# das_updated_v7.net
KiCad netlist of a schematic drawn in EAGLE
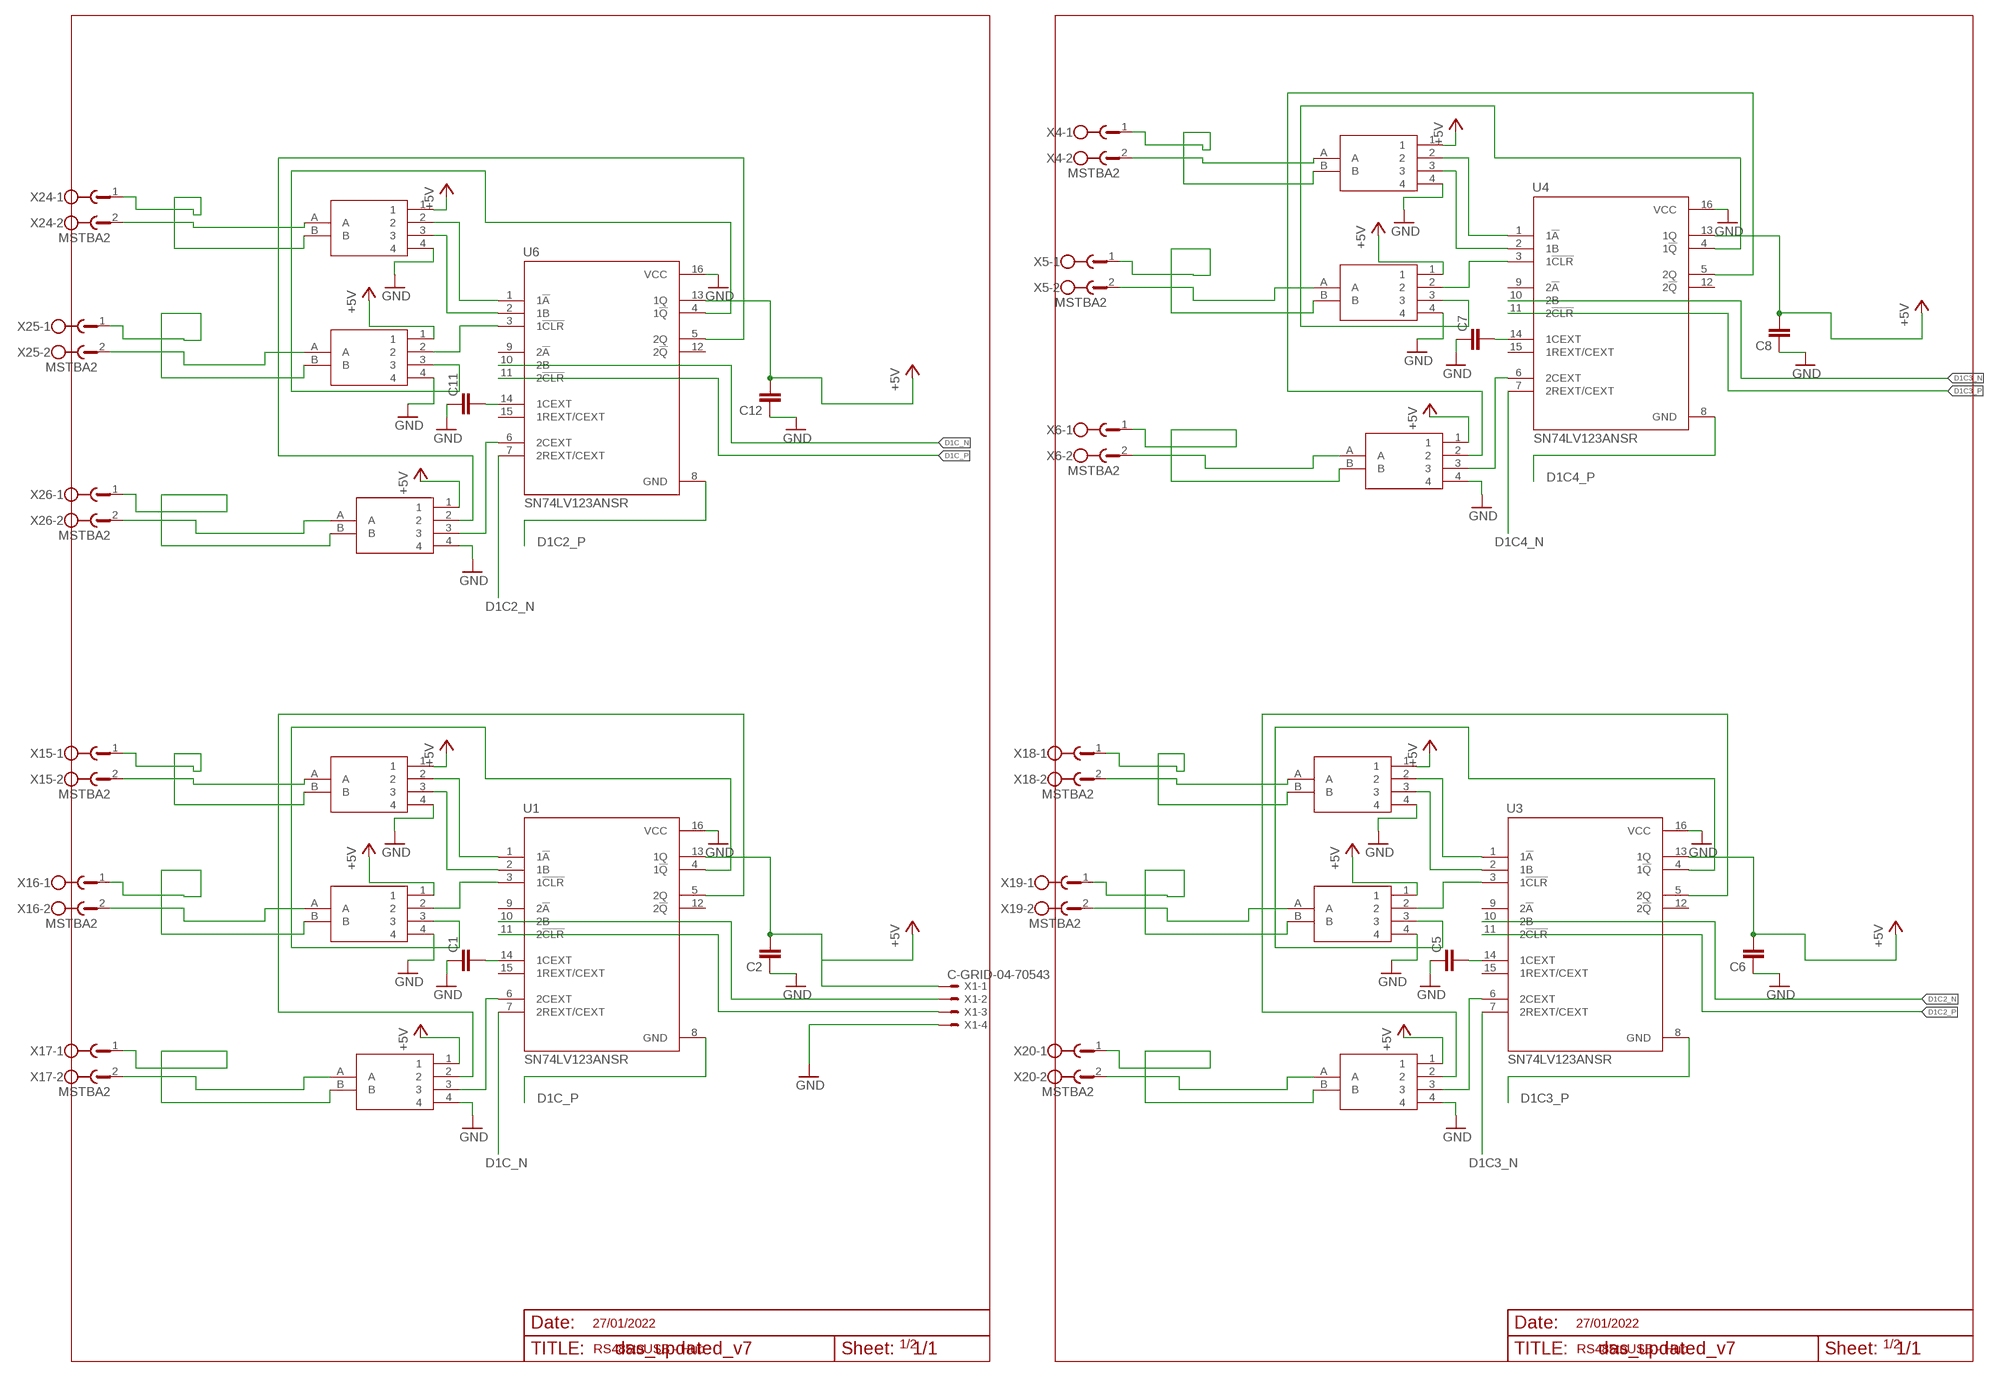
[diagram p0: schematic, sheet 1, part 1 of 2]
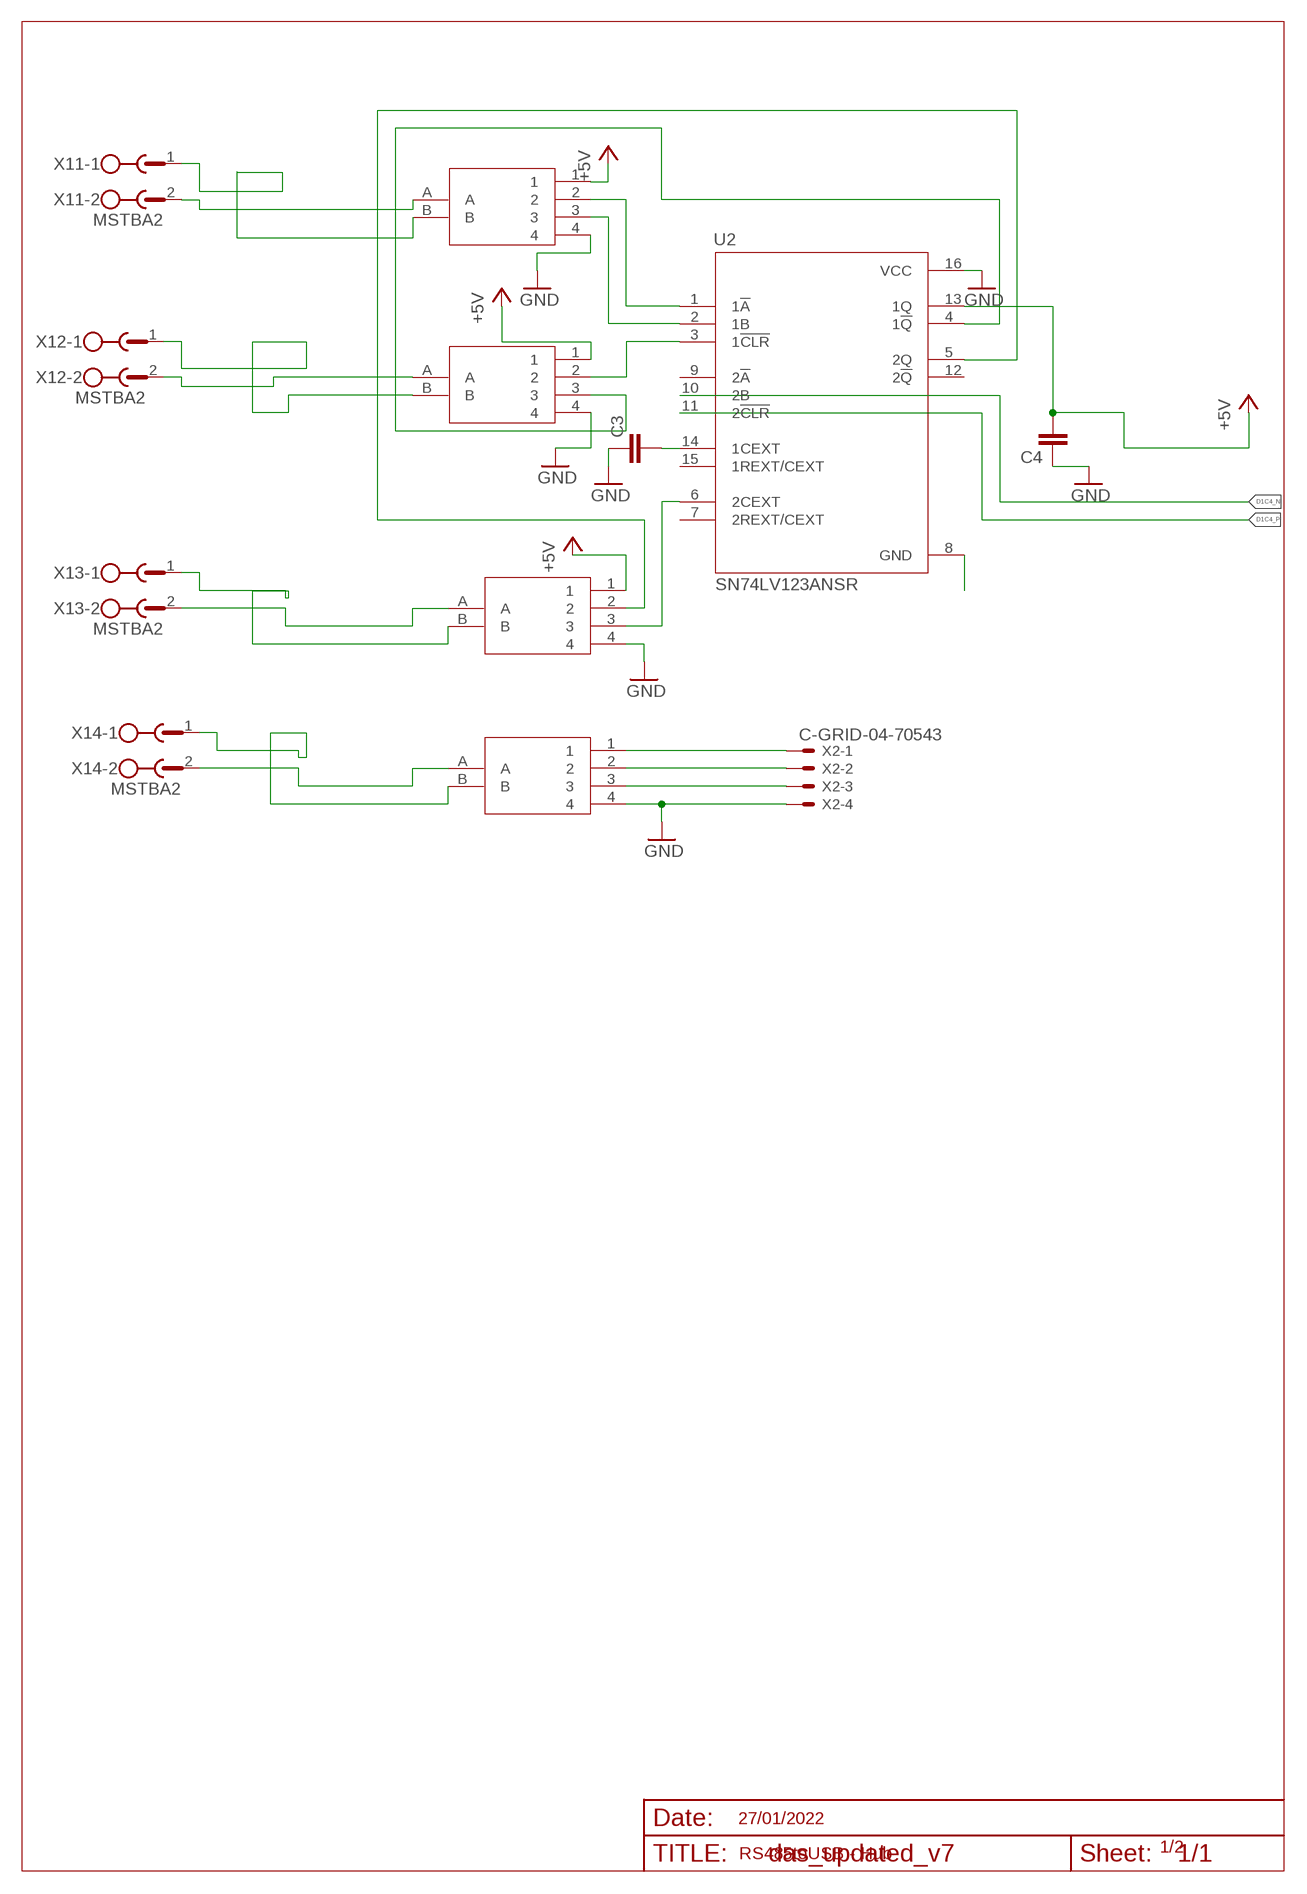
[diagram p1: schematic, sheet 1, part 2 of 2]

(export (version "E")
  (design (tool "Eeschema 10.0.6"))
  (components
    (comp (ref "C1")
      (value "C-EUC0603K")
      (footprint "eagle-import:C0603K")
      (libsource (lib "eagle-import") (part "C-EUC0603K"))
    )
    (comp (ref "C2")
      (value "C-EUC0603K")
      (footprint "eagle-import:C0603K")
      (libsource (lib "eagle-import") (part "C-EUC0603K"))
    )
    (comp (ref "C3")
      (value "C-EUC0603K")
      (footprint "eagle-import:C0603K")
      (libsource (lib "eagle-import") (part "C-EUC0603K"))
    )
    (comp (ref "C4")
      (value "C-EUC0603K")
      (footprint "eagle-import:C0603K")
      (libsource (lib "eagle-import") (part "C-EUC0603K"))
    )
    (comp (ref "C5")
      (value "C-EUC0603K")
      (footprint "eagle-import:C0603K")
      (libsource (lib "eagle-import") (part "C-EUC0603K"))
    )
    (comp (ref "C6")
      (value "C-EUC0603K")
      (footprint "eagle-import:C0603K")
      (libsource (lib "eagle-import") (part "C-EUC0603K"))
    )
    (comp (ref "C7")
      (value "C-EUC0603K")
      (footprint "eagle-import:C0603K")
      (libsource (lib "eagle-import") (part "C-EUC0603K"))
    )
    (comp (ref "C8")
      (value "C-EUC0603K")
      (footprint "eagle-import:C0603K")
      (libsource (lib "eagle-import") (part "C-EUC0603K"))
    )
    (comp (ref "C11")
      (value "C-EUC0603K")
      (footprint "eagle-import:C0603K")
      (libsource (lib "eagle-import") (part "C-EUC0603K"))
    )
    (comp (ref "C12")
      (value "C-EUC0603K")
      (footprint "eagle-import:C0603K")
      (libsource (lib "eagle-import") (part "C-EUC0603K"))
    )
    (comp (ref "U1")
      (value "SN74LV123ANSR")
      (footprint "eagle-import:SOIC127P780X200-16N")
      (fields (field (name "MF") "Texas Instruments"))
      (libsource (lib "eagle-import") (part "SN74LV123ANSR"))
    )
    (comp (ref "U2")
      (value "SN74LV123ANSR")
      (footprint "eagle-import:SOIC127P780X200-16N")
      (fields (field (name "MF") "Texas Instruments"))
      (libsource (lib "eagle-import") (part "SN74LV123ANSR"))
    )
    (comp (ref "U3")
      (value "SN74LV123ANSR")
      (footprint "eagle-import:SOIC127P780X200-16N")
      (fields (field (name "MF") "Texas Instruments"))
      (libsource (lib "eagle-import") (part "SN74LV123ANSR"))
    )
    (comp (ref "U4")
      (value "SN74LV123ANSR")
      (footprint "eagle-import:SOIC127P780X200-16N")
      (fields (field (name "MF") "Texas Instruments"))
      (libsource (lib "eagle-import") (part "SN74LV123ANSR"))
    )
    (comp (ref "U6")
      (value "SN74LV123ANSR")
      (footprint "eagle-import:SOIC127P780X200-16N")
      (fields (field (name "MF") "Texas Instruments"))
      (libsource (lib "eagle-import") (part "SN74LV123ANSR"))
    )
    (comp (ref "USB2RS1")
      (value "USB2RS485")
      (footprint "eagle-import:USB2RS485")
      (libsource (lib "eagle-import") (part "USB2RS485"))
    )
    (comp (ref "USB2RS2")
      (value "USB2RS485")
      (footprint "eagle-import:USB2RS485")
      (libsource (lib "eagle-import") (part "USB2RS485"))
    )
    (comp (ref "USB2RS3")
      (value "USB2RS485")
      (footprint "eagle-import:USB2RS485")
      (libsource (lib "eagle-import") (part "USB2RS485"))
    )
    (comp (ref "USB2RS4")
      (value "USB2RS485")
      (footprint "eagle-import:USB2RS485")
      (libsource (lib "eagle-import") (part "USB2RS485"))
    )
    (comp (ref "USB2RS5")
      (value "USB2RS485")
      (footprint "eagle-import:USB2RS485")
      (libsource (lib "eagle-import") (part "USB2RS485"))
    )
    (comp (ref "USB2RS6")
      (value "USB2RS485")
      (footprint "eagle-import:USB2RS485")
      (libsource (lib "eagle-import") (part "USB2RS485"))
    )
    (comp (ref "USB2RS7")
      (value "USB2RS485")
      (footprint "eagle-import:USB2RS485")
      (libsource (lib "eagle-import") (part "USB2RS485"))
    )
    (comp (ref "USB2RS8")
      (value "USB2RS485")
      (footprint "eagle-import:USB2RS485")
      (libsource (lib "eagle-import") (part "USB2RS485"))
    )
    (comp (ref "USB2RS9")
      (value "USB2RS485")
      (footprint "eagle-import:USB2RS485")
      (libsource (lib "eagle-import") (part "USB2RS485"))
    )
    (comp (ref "USB2RS10")
      (value "USB2RS485")
      (footprint "eagle-import:USB2RS485")
      (libsource (lib "eagle-import") (part "USB2RS485"))
    )
    (comp (ref "USB2RS11")
      (value "USB2RS485")
      (footprint "eagle-import:USB2RS485")
      (libsource (lib "eagle-import") (part "USB2RS485"))
    )
    (comp (ref "USB2RS12")
      (value "USB2RS485")
      (footprint "eagle-import:USB2RS485")
      (libsource (lib "eagle-import") (part "USB2RS485"))
    )
    (comp (ref "USB2RS13")
      (value "USB2RS485")
      (footprint "eagle-import:USB2RS485")
      (libsource (lib "eagle-import") (part "USB2RS485"))
    )
    (comp (ref "USB2RS17")
      (value "USB2RS485")
      (footprint "eagle-import:USB2RS485")
      (libsource (lib "eagle-import") (part "USB2RS485"))
    )
    (comp (ref "USB2RS18")
      (value "USB2RS485")
      (footprint "eagle-import:USB2RS485")
      (libsource (lib "eagle-import") (part "USB2RS485"))
    )
    (comp (ref "USB2RS19")
      (value "USB2RS485")
      (footprint "eagle-import:USB2RS485")
      (libsource (lib "eagle-import") (part "USB2RS485"))
    )
    (comp (ref "X1")
      (value "C-GRID-04-70543")
      (footprint "eagle-import:70543-04")
      (fields (field (name "MF") "MOLEX"))
      (libsource (lib "eagle-import") (part "C-GRID-04-70543"))
    )
    (comp (ref "X2")
      (value "C-GRID-04-70543")
      (footprint "eagle-import:70543-04")
      (fields (field (name "MF") "MOLEX"))
      (libsource (lib "eagle-import") (part "C-GRID-04-70543"))
    )
    (comp (ref "X4")
      (value "MSTBA2")
      (footprint "eagle-import:MSTBA2")
      (fields (field (name "MF") "FARNELL") (field (name "MPN") "1757242"))
      (libsource (lib "eagle-import") (part "MSTBA2"))
    )
    (comp (ref "X5")
      (value "MSTBA2")
      (footprint "eagle-import:MSTBA2")
      (fields (field (name "MF") "FARNELL") (field (name "MPN") "1757242"))
      (libsource (lib "eagle-import") (part "MSTBA2"))
    )
    (comp (ref "X6")
      (value "MSTBA2")
      (footprint "eagle-import:MSTBA2")
      (fields (field (name "MF") "FARNELL") (field (name "MPN") "1757242"))
      (libsource (lib "eagle-import") (part "MSTBA2"))
    )
    (comp (ref "X11")
      (value "MSTBA2")
      (footprint "eagle-import:MSTBA2")
      (fields (field (name "MF") "FARNELL") (field (name "MPN") "1757242"))
      (libsource (lib "eagle-import") (part "MSTBA2"))
    )
    (comp (ref "X12")
      (value "MSTBA2")
      (footprint "eagle-import:MSTBA2")
      (fields (field (name "MF") "FARNELL") (field (name "MPN") "1757242"))
      (libsource (lib "eagle-import") (part "MSTBA2"))
    )
    (comp (ref "X13")
      (value "MSTBA2")
      (footprint "eagle-import:MSTBA2")
      (fields (field (name "MF") "FARNELL") (field (name "MPN") "1757242"))
      (libsource (lib "eagle-import") (part "MSTBA2"))
    )
    (comp (ref "X14")
      (value "MSTBA2")
      (footprint "eagle-import:MSTBA2")
      (fields (field (name "MF") "FARNELL") (field (name "MPN") "1757242"))
      (libsource (lib "eagle-import") (part "MSTBA2"))
    )
    (comp (ref "X15")
      (value "MSTBA2")
      (footprint "eagle-import:MSTBA2")
      (fields (field (name "MF") "FARNELL") (field (name "MPN") "1757242"))
      (libsource (lib "eagle-import") (part "MSTBA2"))
    )
    (comp (ref "X16")
      (value "MSTBA2")
      (footprint "eagle-import:MSTBA2")
      (fields (field (name "MF") "FARNELL") (field (name "MPN") "1757242"))
      (libsource (lib "eagle-import") (part "MSTBA2"))
    )
    (comp (ref "X17")
      (value "MSTBA2")
      (footprint "eagle-import:MSTBA2")
      (fields (field (name "MF") "FARNELL") (field (name "MPN") "1757242"))
      (libsource (lib "eagle-import") (part "MSTBA2"))
    )
    (comp (ref "X18")
      (value "MSTBA2")
      (footprint "eagle-import:MSTBA2")
      (fields (field (name "MF") "FARNELL") (field (name "MPN") "1757242"))
      (libsource (lib "eagle-import") (part "MSTBA2"))
    )
    (comp (ref "X19")
      (value "MSTBA2")
      (footprint "eagle-import:MSTBA2")
      (fields (field (name "MF") "FARNELL") (field (name "MPN") "1757242"))
      (libsource (lib "eagle-import") (part "MSTBA2"))
    )
    (comp (ref "X20")
      (value "MSTBA2")
      (footprint "eagle-import:MSTBA2")
      (fields (field (name "MF") "FARNELL") (field (name "MPN") "1757242"))
      (libsource (lib "eagle-import") (part "MSTBA2"))
    )
    (comp (ref "X24")
      (value "MSTBA2")
      (footprint "eagle-import:MSTBA2")
      (fields (field (name "MF") "FARNELL") (field (name "MPN") "1757242"))
      (libsource (lib "eagle-import") (part "MSTBA2"))
    )
    (comp (ref "X25")
      (value "MSTBA2")
      (footprint "eagle-import:MSTBA2")
      (fields (field (name "MF") "FARNELL") (field (name "MPN") "1757242"))
      (libsource (lib "eagle-import") (part "MSTBA2"))
    )
    (comp (ref "X26")
      (value "MSTBA2")
      (footprint "eagle-import:MSTBA2")
      (fields (field (name "MF") "FARNELL") (field (name "MPN") "1757242"))
      (libsource (lib "eagle-import") (part "MSTBA2"))
    )
  )
  (nets
    (net (code "1") (name "+5V") (class "Default")
      (node (ref "C12") (pin "2") (pinfunction "2_2") (pintype "passive"))
      (node (ref "C2") (pin "2") (pinfunction "2_2") (pintype "passive"))
      (node (ref "C4") (pin "2") (pinfunction "2_2") (pintype "passive"))
      (node (ref "C6") (pin "2") (pinfunction "2_2") (pintype "passive"))
      (node (ref "C8") (pin "2") (pinfunction "2_2") (pintype "passive"))
      (node (ref "U1") (pin "13") (pinfunction "1Q_13") (pintype "output"))
      (node (ref "U2") (pin "13") (pinfunction "1Q_13") (pintype "output"))
      (node (ref "U3") (pin "13") (pinfunction "1Q_13") (pintype "output"))
      (node (ref "U4") (pin "13") (pinfunction "1Q_13") (pintype "output"))
      (node (ref "U6") (pin "13") (pinfunction "1Q_13") (pintype "output"))
      (node (ref "USB2RS1") (pin "1") (pinfunction "1_1") (pintype "bidirectional"))
      (node (ref "USB2RS10") (pin "1") (pinfunction "1_1") (pintype "bidirectional"))
      (node (ref "USB2RS11") (pin "1") (pinfunction "1_1") (pintype "bidirectional"))
      (node (ref "USB2RS12") (pin "1") (pinfunction "1_1") (pintype "bidirectional"))
      (node (ref "USB2RS13") (pin "1") (pinfunction "1_1") (pintype "bidirectional"))
      (node (ref "USB2RS17") (pin "1") (pinfunction "1_1") (pintype "bidirectional"))
      (node (ref "USB2RS18") (pin "1") (pinfunction "1_1") (pintype "bidirectional"))
      (node (ref "USB2RS19") (pin "1") (pinfunction "1_1") (pintype "bidirectional"))
      (node (ref "USB2RS2") (pin "1") (pinfunction "1_1") (pintype "bidirectional"))
      (node (ref "USB2RS3") (pin "1") (pinfunction "1_1") (pintype "bidirectional"))
      (node (ref "USB2RS4") (pin "1") (pinfunction "1_1") (pintype "bidirectional"))
      (node (ref "USB2RS5") (pin "1") (pinfunction "1_1") (pintype "bidirectional"))
      (node (ref "USB2RS6") (pin "1") (pinfunction "1_1") (pintype "bidirectional"))
      (node (ref "USB2RS7") (pin "1") (pinfunction "1_1") (pintype "bidirectional"))
      (node (ref "USB2RS9") (pin "1") (pinfunction "1_1") (pintype "bidirectional"))
      (node (ref "X1") (pin "1") (pinfunction "S_1") (pintype "passive"))
    )
    (net (code "2") (name "D1C2_N") (class "Default")
      (node (ref "U3") (pin "10") (pinfunction "2B_10") (pintype "input"))
      (node (ref "U6") (pin "7") (pinfunction "2REXT/CEXT_7") (pintype "bidirectional"))
    )
    (net (code "3") (name "D1C2_P") (class "Default")
      (node (ref "U3") (pin "11") (pinfunction "2~{CLR}_11") (pintype "input"))
      (node (ref "U6") (pin "8") (pinfunction "GND_8") (pintype "power_in"))
    )
    (net (code "4") (name "D1C3_N") (class "Default")
      (node (ref "U3") (pin "7") (pinfunction "2REXT/CEXT_7") (pintype "bidirectional"))
      (node (ref "U4") (pin "10") (pinfunction "2B_10") (pintype "input"))
    )
    (net (code "5") (name "D1C3_P") (class "Default")
      (node (ref "U3") (pin "8") (pinfunction "GND_8") (pintype "power_in"))
      (node (ref "U4") (pin "11") (pinfunction "2~{CLR}_11") (pintype "input"))
    )
    (net (code "6") (name "D1C4_N") (class "Default")
      (node (ref "U2") (pin "10") (pinfunction "2B_10") (pintype "input"))
      (node (ref "U4") (pin "7") (pinfunction "2REXT/CEXT_7") (pintype "bidirectional"))
    )
    (net (code "7") (name "D1C4_P") (class "Default")
      (node (ref "U2") (pin "11") (pinfunction "2~{CLR}_11") (pintype "input"))
      (node (ref "U4") (pin "8") (pinfunction "GND_8") (pintype "power_in"))
    )
    (net (code "8") (name "D1C_N") (class "Default")
      (node (ref "U1") (pin "7") (pinfunction "2REXT/CEXT_7") (pintype "bidirectional"))
      (node (ref "U6") (pin "10") (pinfunction "2B_10") (pintype "input"))
    )
    (net (code "9") (name "D1C_P") (class "Default")
      (node (ref "U1") (pin "8") (pinfunction "GND_8") (pintype "power_in"))
      (node (ref "U6") (pin "11") (pinfunction "2~{CLR}_11") (pintype "input"))
    )
    (net (code "10") (name "GND") (class "Default")
      (node (ref "C1") (pin "1") (pinfunction "1_1") (pintype "passive"))
      (node (ref "C11") (pin "1") (pinfunction "1_1") (pintype "passive"))
      (node (ref "C12") (pin "1") (pinfunction "1_1") (pintype "passive"))
      (node (ref "C2") (pin "1") (pinfunction "1_1") (pintype "passive"))
      (node (ref "C3") (pin "1") (pinfunction "1_1") (pintype "passive"))
      (node (ref "C4") (pin "1") (pinfunction "1_1") (pintype "passive"))
      (node (ref "C5") (pin "1") (pinfunction "1_1") (pintype "passive"))
      (node (ref "C6") (pin "1") (pinfunction "1_1") (pintype "passive"))
      (node (ref "C7") (pin "1") (pinfunction "1_1") (pintype "passive"))
      (node (ref "C8") (pin "1") (pinfunction "1_1") (pintype "passive"))
      (node (ref "U1") (pin "16") (pinfunction "VCC_16") (pintype "power_in"))
      (node (ref "U2") (pin "16") (pinfunction "VCC_16") (pintype "power_in"))
      (node (ref "U3") (pin "16") (pinfunction "VCC_16") (pintype "power_in"))
      (node (ref "U4") (pin "16") (pinfunction "VCC_16") (pintype "power_in"))
      (node (ref "U6") (pin "16") (pinfunction "VCC_16") (pintype "power_in"))
      (node (ref "USB2RS1") (pin "4") (pinfunction "4_4") (pintype "bidirectional"))
      (node (ref "USB2RS10") (pin "4") (pinfunction "4_4") (pintype "bidirectional"))
      (node (ref "USB2RS11") (pin "4") (pinfunction "4_4") (pintype "bidirectional"))
      (node (ref "USB2RS12") (pin "4") (pinfunction "4_4") (pintype "bidirectional"))
      (node (ref "USB2RS13") (pin "4") (pinfunction "4_4") (pintype "bidirectional"))
      (node (ref "USB2RS17") (pin "4") (pinfunction "4_4") (pintype "bidirectional"))
      (node (ref "USB2RS18") (pin "4") (pinfunction "4_4") (pintype "bidirectional"))
      (node (ref "USB2RS19") (pin "4") (pinfunction "4_4") (pintype "bidirectional"))
      (node (ref "USB2RS2") (pin "4") (pinfunction "4_4") (pintype "bidirectional"))
      (node (ref "USB2RS3") (pin "4") (pinfunction "4_4") (pintype "bidirectional"))
      (node (ref "USB2RS4") (pin "4") (pinfunction "4_4") (pintype "bidirectional"))
      (node (ref "USB2RS5") (pin "4") (pinfunction "4_4") (pintype "bidirectional"))
      (node (ref "USB2RS6") (pin "4") (pinfunction "4_4") (pintype "bidirectional"))
      (node (ref "USB2RS7") (pin "4") (pinfunction "4_4") (pintype "bidirectional"))
      (node (ref "USB2RS8") (pin "4") (pinfunction "4_4") (pintype "bidirectional"))
      (node (ref "USB2RS9") (pin "4") (pinfunction "4_4") (pintype "bidirectional"))
      (node (ref "X1") (pin "4") (pinfunction "S_4") (pintype "passive"))
      (node (ref "X2") (pin "4") (pinfunction "S_4") (pintype "passive"))
    )
    (net (code "11") (name "Net-(U1-1B)") (class "Default")
      (node (ref "U1") (pin "2") (pinfunction "1B_2") (pintype "input"))
      (node (ref "USB2RS1") (pin "3") (pinfunction "3_3") (pintype "bidirectional"))
    )
    (net (code "12") (name "Net-(U1-1CEXT)") (class "Default")
      (node (ref "C1") (pin "2") (pinfunction "2_2") (pintype "passive"))
      (node (ref "U1") (pin "14") (pinfunction "1CEXT_14") (pintype "bidirectional"))
    )
    (net (code "13") (name "Net-(U1-1~{A})") (class "Default")
      (node (ref "U1") (pin "1") (pinfunction "1~{A}_1") (pintype "input"))
      (node (ref "USB2RS1") (pin "2") (pinfunction "2_2") (pintype "bidirectional"))
    )
    (net (code "14") (name "Net-(U1-1~{CLR})") (class "Default")
      (node (ref "U1") (pin "3") (pinfunction "1~{CLR}_3") (pintype "input"))
      (node (ref "USB2RS2") (pin "2") (pinfunction "2_2") (pintype "bidirectional"))
    )
    (net (code "15") (name "Net-(U1-1~{Q})") (class "Default")
      (node (ref "U1") (pin "4") (pinfunction "1~{Q}_4") (pintype "output"))
      (node (ref "USB2RS2") (pin "3") (pinfunction "3_3") (pintype "bidirectional"))
    )
    (net (code "16") (name "Net-(U1-2B)") (class "Default")
      (node (ref "U1") (pin "10") (pinfunction "2B_10") (pintype "input"))
      (node (ref "X1") (pin "2") (pinfunction "S_2") (pintype "passive"))
    )
    (net (code "17") (name "Net-(U1-2CEXT)") (class "Default")
      (node (ref "U1") (pin "6") (pinfunction "2CEXT_6") (pintype "bidirectional"))
      (node (ref "USB2RS3") (pin "3") (pinfunction "3_3") (pintype "bidirectional"))
    )
    (net (code "18") (name "Net-(U1-2Q)") (class "Default")
      (node (ref "U1") (pin "5") (pinfunction "2Q_5") (pintype "output"))
      (node (ref "USB2RS3") (pin "2") (pinfunction "2_2") (pintype "bidirectional"))
    )
    (net (code "19") (name "Net-(U1-2~{CLR})") (class "Default")
      (node (ref "U1") (pin "11") (pinfunction "2~{CLR}_11") (pintype "input"))
      (node (ref "X1") (pin "3") (pinfunction "S_3") (pintype "passive"))
    )
    (net (code "20") (name "Net-(U2-1B)") (class "Default")
      (node (ref "U2") (pin "2") (pinfunction "1B_2") (pintype "input"))
      (node (ref "USB2RS5") (pin "3") (pinfunction "3_3") (pintype "bidirectional"))
    )
    (net (code "21") (name "Net-(U2-1CEXT)") (class "Default")
      (node (ref "C3") (pin "2") (pinfunction "2_2") (pintype "passive"))
      (node (ref "U2") (pin "14") (pinfunction "1CEXT_14") (pintype "bidirectional"))
    )
    (net (code "22") (name "Net-(U2-1~{A})") (class "Default")
      (node (ref "U2") (pin "1") (pinfunction "1~{A}_1") (pintype "input"))
      (node (ref "USB2RS5") (pin "2") (pinfunction "2_2") (pintype "bidirectional"))
    )
    (net (code "23") (name "Net-(U2-1~{CLR})") (class "Default")
      (node (ref "U2") (pin "3") (pinfunction "1~{CLR}_3") (pintype "input"))
      (node (ref "USB2RS6") (pin "2") (pinfunction "2_2") (pintype "bidirectional"))
    )
    (net (code "24") (name "Net-(U2-1~{Q})") (class "Default")
      (node (ref "U2") (pin "4") (pinfunction "1~{Q}_4") (pintype "output"))
      (node (ref "USB2RS6") (pin "3") (pinfunction "3_3") (pintype "bidirectional"))
    )
    (net (code "25") (name "Net-(U2-2CEXT)") (class "Default")
      (node (ref "U2") (pin "6") (pinfunction "2CEXT_6") (pintype "bidirectional"))
      (node (ref "USB2RS7") (pin "3") (pinfunction "3_3") (pintype "bidirectional"))
    )
    (net (code "26") (name "Net-(U2-2Q)") (class "Default")
      (node (ref "U2") (pin "5") (pinfunction "2Q_5") (pintype "output"))
      (node (ref "USB2RS7") (pin "2") (pinfunction "2_2") (pintype "bidirectional"))
    )
    (net (code "27") (name "Net-(U3-1B)") (class "Default")
      (node (ref "U3") (pin "2") (pinfunction "1B_2") (pintype "input"))
      (node (ref "USB2RS4") (pin "3") (pinfunction "3_3") (pintype "bidirectional"))
    )
    (net (code "28") (name "Net-(U3-1CEXT)") (class "Default")
      (node (ref "C5") (pin "2") (pinfunction "2_2") (pintype "passive"))
      (node (ref "U3") (pin "14") (pinfunction "1CEXT_14") (pintype "bidirectional"))
    )
    (net (code "29") (name "Net-(U3-1~{A})") (class "Default")
      (node (ref "U3") (pin "1") (pinfunction "1~{A}_1") (pintype "input"))
      (node (ref "USB2RS4") (pin "2") (pinfunction "2_2") (pintype "bidirectional"))
    )
    (net (code "30") (name "Net-(U3-1~{CLR})") (class "Default")
      (node (ref "U3") (pin "3") (pinfunction "1~{CLR}_3") (pintype "input"))
      (node (ref "USB2RS9") (pin "2") (pinfunction "2_2") (pintype "bidirectional"))
    )
    (net (code "31") (name "Net-(U3-1~{Q})") (class "Default")
      (node (ref "U3") (pin "4") (pinfunction "1~{Q}_4") (pintype "output"))
      (node (ref "USB2RS9") (pin "3") (pinfunction "3_3") (pintype "bidirectional"))
    )
    (net (code "32") (name "Net-(U3-2CEXT)") (class "Default")
      (node (ref "U3") (pin "6") (pinfunction "2CEXT_6") (pintype "bidirectional"))
      (node (ref "USB2RS10") (pin "3") (pinfunction "3_3") (pintype "bidirectional"))
    )
    (net (code "33") (name "Net-(U3-2Q)") (class "Default")
      (node (ref "U3") (pin "5") (pinfunction "2Q_5") (pintype "output"))
      (node (ref "USB2RS10") (pin "2") (pinfunction "2_2") (pintype "bidirectional"))
    )
    (net (code "34") (name "Net-(U4-1B)") (class "Default")
      (node (ref "U4") (pin "2") (pinfunction "1B_2") (pintype "input"))
      (node (ref "USB2RS11") (pin "3") (pinfunction "3_3") (pintype "bidirectional"))
    )
    (net (code "35") (name "Net-(U4-1CEXT)") (class "Default")
      (node (ref "C7") (pin "2") (pinfunction "2_2") (pintype "passive"))
      (node (ref "U4") (pin "14") (pinfunction "1CEXT_14") (pintype "bidirectional"))
    )
    (net (code "36") (name "Net-(U4-1~{A})") (class "Default")
      (node (ref "U4") (pin "1") (pinfunction "1~{A}_1") (pintype "input"))
      (node (ref "USB2RS11") (pin "2") (pinfunction "2_2") (pintype "bidirectional"))
    )
    (net (code "37") (name "Net-(U4-1~{CLR})") (class "Default")
      (node (ref "U4") (pin "3") (pinfunction "1~{CLR}_3") (pintype "input"))
      (node (ref "USB2RS12") (pin "2") (pinfunction "2_2") (pintype "bidirectional"))
    )
    (net (code "38") (name "Net-(U4-1~{Q})") (class "Default")
      (node (ref "U4") (pin "4") (pinfunction "1~{Q}_4") (pintype "output"))
      (node (ref "USB2RS12") (pin "3") (pinfunction "3_3") (pintype "bidirectional"))
    )
    (net (code "39") (name "Net-(U4-2CEXT)") (class "Default")
      (node (ref "U4") (pin "6") (pinfunction "2CEXT_6") (pintype "bidirectional"))
      (node (ref "USB2RS13") (pin "3") (pinfunction "3_3") (pintype "bidirectional"))
    )
    (net (code "40") (name "Net-(U4-2Q)") (class "Default")
      (node (ref "U4") (pin "5") (pinfunction "2Q_5") (pintype "output"))
      (node (ref "USB2RS13") (pin "2") (pinfunction "2_2") (pintype "bidirectional"))
    )
    (net (code "41") (name "Net-(U6-1B)") (class "Default")
      (node (ref "U6") (pin "2") (pinfunction "1B_2") (pintype "input"))
      (node (ref "USB2RS17") (pin "3") (pinfunction "3_3") (pintype "bidirectional"))
    )
    (net (code "42") (name "Net-(U6-1CEXT)") (class "Default")
      (node (ref "C11") (pin "2") (pinfunction "2_2") (pintype "passive"))
      (node (ref "U6") (pin "14") (pinfunction "1CEXT_14") (pintype "bidirectional"))
    )
    (net (code "43") (name "Net-(U6-1~{A})") (class "Default")
      (node (ref "U6") (pin "1") (pinfunction "1~{A}_1") (pintype "input"))
      (node (ref "USB2RS17") (pin "2") (pinfunction "2_2") (pintype "bidirectional"))
    )
    (net (code "44") (name "Net-(U6-1~{CLR})") (class "Default")
      (node (ref "U6") (pin "3") (pinfunction "1~{CLR}_3") (pintype "input"))
      (node (ref "USB2RS18") (pin "2") (pinfunction "2_2") (pintype "bidirectional"))
    )
    (net (code "45") (name "Net-(U6-1~{Q})") (class "Default")
      (node (ref "U6") (pin "4") (pinfunction "1~{Q}_4") (pintype "output"))
      (node (ref "USB2RS18") (pin "3") (pinfunction "3_3") (pintype "bidirectional"))
    )
    (net (code "46") (name "Net-(U6-2CEXT)") (class "Default")
      (node (ref "U6") (pin "6") (pinfunction "2CEXT_6") (pintype "bidirectional"))
      (node (ref "USB2RS19") (pin "3") (pinfunction "3_3") (pintype "bidirectional"))
    )
    (net (code "47") (name "Net-(U6-2Q)") (class "Default")
      (node (ref "U6") (pin "5") (pinfunction "2Q_5") (pintype "output"))
      (node (ref "USB2RS19") (pin "2") (pinfunction "2_2") (pintype "bidirectional"))
    )
    (net (code "48") (name "Net-(USB2RS1-PadB)") (class "Default")
      (node (ref "USB2RS1") (pin "B") (pinfunction "B_B") (pintype "bidirectional"))
      (node (ref "X15") (pin "1") (pinfunction "1_1") (pintype "passive"))
    )
    (net (code "49") (name "Net-(USB2RS2-PadB)") (class "Default")
      (node (ref "USB2RS2") (pin "B") (pinfunction "B_B") (pintype "bidirectional"))
      (node (ref "X16") (pin "1") (pinfunction "1_1") (pintype "passive"))
    )
    (net (code "50") (name "Net-(USB2RS3-PadB)") (class "Default")
      (node (ref "USB2RS3") (pin "B") (pinfunction "B_B") (pintype "bidirectional"))
      (node (ref "X17") (pin "1") (pinfunction "1_1") (pintype "passive"))
    )
    (net (code "51") (name "Net-(USB2RS4-PadB)") (class "Default")
      (node (ref "USB2RS4") (pin "B") (pinfunction "B_B") (pintype "bidirectional"))
      (node (ref "X18") (pin "1") (pinfunction "1_1") (pintype "passive"))
    )
    (net (code "52") (name "Net-(USB2RS5-PadB)") (class "Default")
      (node (ref "USB2RS5") (pin "B") (pinfunction "B_B") (pintype "bidirectional"))
      (node (ref "X11") (pin "1") (pinfunction "1_1") (pintype "passive"))
    )
    (net (code "53") (name "Net-(USB2RS6-PadB)") (class "Default")
      (node (ref "USB2RS6") (pin "B") (pinfunction "B_B") (pintype "bidirectional"))
      (node (ref "X12") (pin "1") (pinfunction "1_1") (pintype "passive"))
    )
    (net (code "54") (name "Net-(USB2RS7-PadB)") (class "Default")
      (node (ref "USB2RS7") (pin "B") (pinfunction "B_B") (pintype "bidirectional"))
      (node (ref "X13") (pin "1") (pinfunction "1_1") (pintype "passive"))
    )
    (net (code "55") (name "Net-(USB2RS8-PadB)") (class "Default")
      (node (ref "USB2RS8") (pin "B") (pinfunction "B_B") (pintype "bidirectional"))
      (node (ref "X14") (pin "1") (pinfunction "1_1") (pintype "passive"))
    )
    (net (code "56") (name "Net-(USB2RS9-PadB)") (class "Default")
      (node (ref "USB2RS9") (pin "B") (pinfunction "B_B") (pintype "bidirectional"))
      (node (ref "X19") (pin "1") (pinfunction "1_1") (pintype "passive"))
    )
    (net (code "57") (name "Net-(USB2RS10-PadB)") (class "Default")
      (node (ref "USB2RS10") (pin "B") (pinfunction "B_B") (pintype "bidirectional"))
      (node (ref "X20") (pin "1") (pinfunction "1_1") (pintype "passive"))
    )
    (net (code "58") (name "Net-(USB2RS11-PadB)") (class "Default")
      (node (ref "USB2RS11") (pin "B") (pinfunction "B_B") (pintype "bidirectional"))
      (node (ref "X4") (pin "1") (pinfunction "1_1") (pintype "passive"))
    )
    (net (code "59") (name "Net-(USB2RS12-PadB)") (class "Default")
      (node (ref "USB2RS12") (pin "B") (pinfunction "B_B") (pintype "bidirectional"))
      (node (ref "X5") (pin "1") (pinfunction "1_1") (pintype "passive"))
    )
    (net (code "60") (name "Net-(USB2RS13-PadB)") (class "Default")
      (node (ref "USB2RS13") (pin "B") (pinfunction "B_B") (pintype "bidirectional"))
      (node (ref "X6") (pin "1") (pinfunction "1_1") (pintype "passive"))
    )
    (net (code "61") (name "Net-(USB2RS17-PadB)") (class "Default")
      (node (ref "USB2RS17") (pin "B") (pinfunction "B_B") (pintype "bidirectional"))
      (node (ref "X24") (pin "1") (pinfunction "1_1") (pintype "passive"))
    )
    (net (code "62") (name "Net-(USB2RS18-PadB)") (class "Default")
      (node (ref "USB2RS18") (pin "B") (pinfunction "B_B") (pintype "bidirectional"))
      (node (ref "X25") (pin "1") (pinfunction "1_1") (pintype "passive"))
    )
    (net (code "63") (name "Net-(USB2RS19-PadB)") (class "Default")
      (node (ref "USB2RS19") (pin "B") (pinfunction "B_B") (pintype "bidirectional"))
      (node (ref "X26") (pin "1") (pinfunction "1_1") (pintype "passive"))
    )
    (net (code "64") (name "Net-(X2A-S)") (class "Default")
      (node (ref "USB2RS8") (pin "1") (pinfunction "1_1") (pintype "bidirectional"))
      (node (ref "X2") (pin "1") (pinfunction "S_1") (pintype "passive"))
    )
    (net (code "65") (name "Net-(X2B-S)") (class "Default")
      (node (ref "USB2RS8") (pin "2") (pinfunction "2_2") (pintype "bidirectional"))
      (node (ref "X2") (pin "2") (pinfunction "S_2") (pintype "passive"))
    )
    (net (code "66") (name "Net-(X2C-S)") (class "Default")
      (node (ref "USB2RS8") (pin "3") (pinfunction "3_3") (pintype "bidirectional"))
      (node (ref "X2") (pin "3") (pinfunction "S_3") (pintype "passive"))
    )
    (net (code "67") (name "Net-(X4B-1)") (class "Default")
      (node (ref "USB2RS11") (pin "A") (pinfunction "A_A") (pintype "bidirectional"))
      (node (ref "X4") (pin "2") (pinfunction "1_2") (pintype "passive"))
    )
    (net (code "68") (name "Net-(X5B-1)") (class "Default")
      (node (ref "USB2RS12") (pin "A") (pinfunction "A_A") (pintype "bidirectional"))
      (node (ref "X5") (pin "2") (pinfunction "1_2") (pintype "passive"))
    )
    (net (code "69") (name "Net-(X6B-1)") (class "Default")
      (node (ref "USB2RS13") (pin "A") (pinfunction "A_A") (pintype "bidirectional"))
      (node (ref "X6") (pin "2") (pinfunction "1_2") (pintype "passive"))
    )
    (net (code "70") (name "Net-(X11B-1)") (class "Default")
      (node (ref "USB2RS5") (pin "A") (pinfunction "A_A") (pintype "bidirectional"))
      (node (ref "X11") (pin "2") (pinfunction "1_2") (pintype "passive"))
    )
    (net (code "71") (name "Net-(X12B-1)") (class "Default")
      (node (ref "USB2RS6") (pin "A") (pinfunction "A_A") (pintype "bidirectional"))
      (node (ref "X12") (pin "2") (pinfunction "1_2") (pintype "passive"))
    )
    (net (code "72") (name "Net-(X13B-1)") (class "Default")
      (node (ref "USB2RS7") (pin "A") (pinfunction "A_A") (pintype "bidirectional"))
      (node (ref "X13") (pin "2") (pinfunction "1_2") (pintype "passive"))
    )
    (net (code "73") (name "Net-(X14B-1)") (class "Default")
      (node (ref "USB2RS8") (pin "A") (pinfunction "A_A") (pintype "bidirectional"))
      (node (ref "X14") (pin "2") (pinfunction "1_2") (pintype "passive"))
    )
    (net (code "74") (name "Net-(X15B-1)") (class "Default")
      (node (ref "USB2RS1") (pin "A") (pinfunction "A_A") (pintype "bidirectional"))
      (node (ref "X15") (pin "2") (pinfunction "1_2") (pintype "passive"))
    )
    (net (code "75") (name "Net-(X16B-1)") (class "Default")
      (node (ref "USB2RS2") (pin "A") (pinfunction "A_A") (pintype "bidirectional"))
      (node (ref "X16") (pin "2") (pinfunction "1_2") (pintype "passive"))
    )
    (net (code "76") (name "Net-(X17B-1)") (class "Default")
      (node (ref "USB2RS3") (pin "A") (pinfunction "A_A") (pintype "bidirectional"))
      (node (ref "X17") (pin "2") (pinfunction "1_2") (pintype "passive"))
    )
    (net (code "77") (name "Net-(X18B-1)") (class "Default")
      (node (ref "USB2RS4") (pin "A") (pinfunction "A_A") (pintype "bidirectional"))
      (node (ref "X18") (pin "2") (pinfunction "1_2") (pintype "passive"))
    )
    (net (code "78") (name "Net-(X19B-1)") (class "Default")
      (node (ref "USB2RS9") (pin "A") (pinfunction "A_A") (pintype "bidirectional"))
      (node (ref "X19") (pin "2") (pinfunction "1_2") (pintype "passive"))
    )
    (net (code "79") (name "Net-(X20B-1)") (class "Default")
      (node (ref "USB2RS10") (pin "A") (pinfunction "A_A") (pintype "bidirectional"))
      (node (ref "X20") (pin "2") (pinfunction "1_2") (pintype "passive"))
    )
    (net (code "80") (name "Net-(X24B-1)") (class "Default")
      (node (ref "USB2RS17") (pin "A") (pinfunction "A_A") (pintype "bidirectional"))
      (node (ref "X24") (pin "2") (pinfunction "1_2") (pintype "passive"))
    )
    (net (code "81") (name "Net-(X25B-1)") (class "Default")
      (node (ref "USB2RS18") (pin "A") (pinfunction "A_A") (pintype "bidirectional"))
      (node (ref "X25") (pin "2") (pinfunction "1_2") (pintype "passive"))
    )
    (net (code "82") (name "Net-(X26B-1)") (class "Default")
      (node (ref "USB2RS19") (pin "A") (pinfunction "A_A") (pintype "bidirectional"))
      (node (ref "X26") (pin "2") (pinfunction "1_2") (pintype "passive"))
    )
    (net (code "83") (name "unconnected-(U1-1REXT{slash}CEXT-Pad15)") (class "Default")
      (node (ref "U1") (pin "15") (pinfunction "1REXT/CEXT_15") (pintype "bidirectional"))
    )
    (net (code "84") (name "unconnected-(U1-2~{A}-Pad9)") (class "Default")
      (node (ref "U1") (pin "9") (pinfunction "2~{A}_9") (pintype "input"))
    )
    (net (code "85") (name "unconnected-(U1-2~{Q}-Pad12)") (class "Default")
      (node (ref "U1") (pin "12") (pinfunction "2~{Q}_12") (pintype "output"))
    )
    (net (code "86") (name "unconnected-(U2-1REXT{slash}CEXT-Pad15)") (class "Default")
      (node (ref "U2") (pin "15") (pinfunction "1REXT/CEXT_15") (pintype "bidirectional"))
    )
    (net (code "87") (name "unconnected-(U2-2REXT{slash}CEXT-Pad7)") (class "Default")
      (node (ref "U2") (pin "7") (pinfunction "2REXT/CEXT_7") (pintype "bidirectional"))
    )
    (net (code "88") (name "unconnected-(U2-2~{A}-Pad9)") (class "Default")
      (node (ref "U2") (pin "9") (pinfunction "2~{A}_9") (pintype "input"))
    )
    (net (code "89") (name "unconnected-(U2-2~{Q}-Pad12)") (class "Default")
      (node (ref "U2") (pin "12") (pinfunction "2~{Q}_12") (pintype "output"))
    )
    (net (code "90") (name "unconnected-(U2-GND-Pad8)") (class "Default")
      (node (ref "U2") (pin "8") (pinfunction "GND_8") (pintype "power_in"))
    )
    (net (code "91") (name "unconnected-(U3-1REXT{slash}CEXT-Pad15)") (class "Default")
      (node (ref "U3") (pin "15") (pinfunction "1REXT/CEXT_15") (pintype "bidirectional"))
    )
    (net (code "92") (name "unconnected-(U3-2~{A}-Pad9)") (class "Default")
      (node (ref "U3") (pin "9") (pinfunction "2~{A}_9") (pintype "input"))
    )
    (net (code "93") (name "unconnected-(U3-2~{Q}-Pad12)") (class "Default")
      (node (ref "U3") (pin "12") (pinfunction "2~{Q}_12") (pintype "output"))
    )
    (net (code "94") (name "unconnected-(U4-1REXT{slash}CEXT-Pad15)") (class "Default")
      (node (ref "U4") (pin "15") (pinfunction "1REXT/CEXT_15") (pintype "bidirectional"))
    )
    (net (code "95") (name "unconnected-(U4-2~{A}-Pad9)") (class "Default")
      (node (ref "U4") (pin "9") (pinfunction "2~{A}_9") (pintype "input"))
    )
    (net (code "96") (name "unconnected-(U4-2~{Q}-Pad12)") (class "Default")
      (node (ref "U4") (pin "12") (pinfunction "2~{Q}_12") (pintype "output"))
    )
    (net (code "97") (name "unconnected-(U6-1REXT{slash}CEXT-Pad15)") (class "Default")
      (node (ref "U6") (pin "15") (pinfunction "1REXT/CEXT_15") (pintype "bidirectional"))
    )
    (net (code "98") (name "unconnected-(U6-2~{A}-Pad9)") (class "Default")
      (node (ref "U6") (pin "9") (pinfunction "2~{A}_9") (pintype "input"))
    )
    (net (code "99") (name "unconnected-(U6-2~{Q}-Pad12)") (class "Default")
      (node (ref "U6") (pin "12") (pinfunction "2~{Q}_12") (pintype "output"))
    )
  )
)
